# CD4046-DIP16.net
KiCad netlist of a schematic drawn in Altium Designer
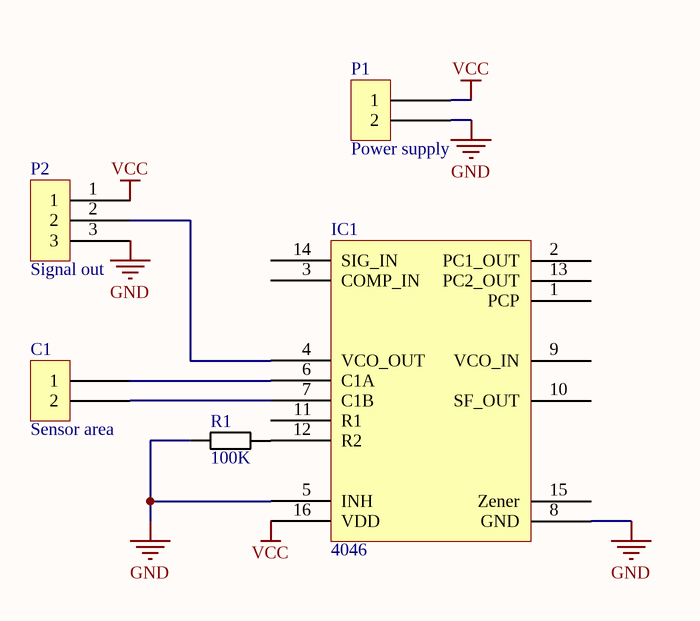
[diagram p0: CD4046-DIP16.SchDoc]

(export (version "E")
  (design (tool "Eeschema 10.0.6"))
  (components
    (comp (ref "C1")
      (value "Sensor area")
      (footprint "Header 2x1 long")
      (libsource (lib "Headers") (part "Header 2x1"))
    )
    (comp (ref "IC1")
      (value "4046")
      (footprint "DIP-16")
      (description "PLL / VCO")
      (libsource (lib "ICs") (part "4046"))
    )
    (comp (ref "P1")
      (value "Power supply")
      (footprint "Header 2x1 long")
      (libsource (lib "Headers") (part "Header 2x1"))
    )
    (comp (ref "P2")
      (value "Signal out")
      (footprint "Header 3x1 long")
      (description "2.54mm")
      (libsource (lib "Headers") (part "Header 1x3"))
    )
    (comp (ref "R1")
      (value "100K")
      (footprint "R 0805 / 2012")
      (libsource (lib "Standard") (part "Resistor"))
    )
  )
  (nets
    (net (code "1") (name "GND") (class "Default")
      (node (ref "IC1") (pin "5") (pinfunction "INH_5") (pintype "passive"))
      (node (ref "IC1") (pin "8") (pinfunction "GND_8") (pintype "passive"))
      (node (ref "P1") (pin "2") (pinfunction "2_2") (pintype "passive"))
      (node (ref "P2") (pin "3") (pinfunction "3_3") (pintype "passive"))
      (node (ref "R1") (pin "2") (pinfunction "2_2") (pintype "passive"))
    )
    (net (code "2") (name "Net-(IC1-C1A)") (class "Default")
      (node (ref "C1") (pin "1") (pinfunction "1_1") (pintype "passive"))
      (node (ref "IC1") (pin "6") (pinfunction "C1A_6") (pintype "passive"))
    )
    (net (code "3") (name "Net-(IC1-C1B)") (class "Default")
      (node (ref "C1") (pin "2") (pinfunction "2_2") (pintype "passive"))
      (node (ref "IC1") (pin "7") (pinfunction "C1B_7") (pintype "passive"))
    )
    (net (code "4") (name "Net-(IC1-R2)") (class "Default")
      (node (ref "IC1") (pin "12") (pinfunction "R2_12") (pintype "passive"))
      (node (ref "R1") (pin "1") (pinfunction "1_1") (pintype "passive"))
    )
    (net (code "5") (name "Net-(IC1-VCO_OUT)") (class "Default")
      (node (ref "IC1") (pin "4") (pinfunction "VCO_OUT_4") (pintype "passive"))
      (node (ref "P2") (pin "2") (pinfunction "2_2") (pintype "passive"))
    )
    (net (code "6") (name "VCC") (class "Default")
      (node (ref "IC1") (pin "16") (pinfunction "VDD_16") (pintype "passive"))
      (node (ref "P1") (pin "1") (pinfunction "1_1") (pintype "passive"))
      (node (ref "P2") (pin "1") (pinfunction "1_1") (pintype "passive"))
    )
    (net (code "7") (name "unconnected-(IC1-COMP_IN-Pad3)") (class "Default")
      (node (ref "IC1") (pin "3") (pinfunction "COMP_IN_3") (pintype "passive"))
    )
    (net (code "8") (name "unconnected-(IC1-PC1_OUT-Pad2)") (class "Default")
      (node (ref "IC1") (pin "2") (pinfunction "PC1_OUT_2") (pintype "passive"))
    )
    (net (code "9") (name "unconnected-(IC1-PC2_OUT-Pad13)") (class "Default")
      (node (ref "IC1") (pin "13") (pinfunction "PC2_OUT_13") (pintype "passive"))
    )
    (net (code "10") (name "unconnected-(IC1-PCP-Pad1)") (class "Default")
      (node (ref "IC1") (pin "1") (pinfunction "PCP_1") (pintype "passive"))
    )
    (net (code "11") (name "unconnected-(IC1-R1-Pad11)") (class "Default")
      (node (ref "IC1") (pin "11") (pinfunction "R1_11") (pintype "passive"))
    )
    (net (code "12") (name "unconnected-(IC1-SF_OUT-Pad10)") (class "Default")
      (node (ref "IC1") (pin "10") (pinfunction "SF_OUT_10") (pintype "passive"))
    )
    (net (code "13") (name "unconnected-(IC1-SIG_IN-Pad14)") (class "Default")
      (node (ref "IC1") (pin "14") (pinfunction "SIG_IN_14") (pintype "passive"))
    )
    (net (code "14") (name "unconnected-(IC1-VCO_IN-Pad9)") (class "Default")
      (node (ref "IC1") (pin "9") (pinfunction "VCO_IN_9") (pintype "passive"))
    )
    (net (code "15") (name "unconnected-(IC1-Zener-Pad15)") (class "Default")
      (node (ref "IC1") (pin "15") (pinfunction "Zener_15") (pintype "passive"))
    )
  )
)
